# PT.net
KiCad netlist of a schematic drawn in EAGLE
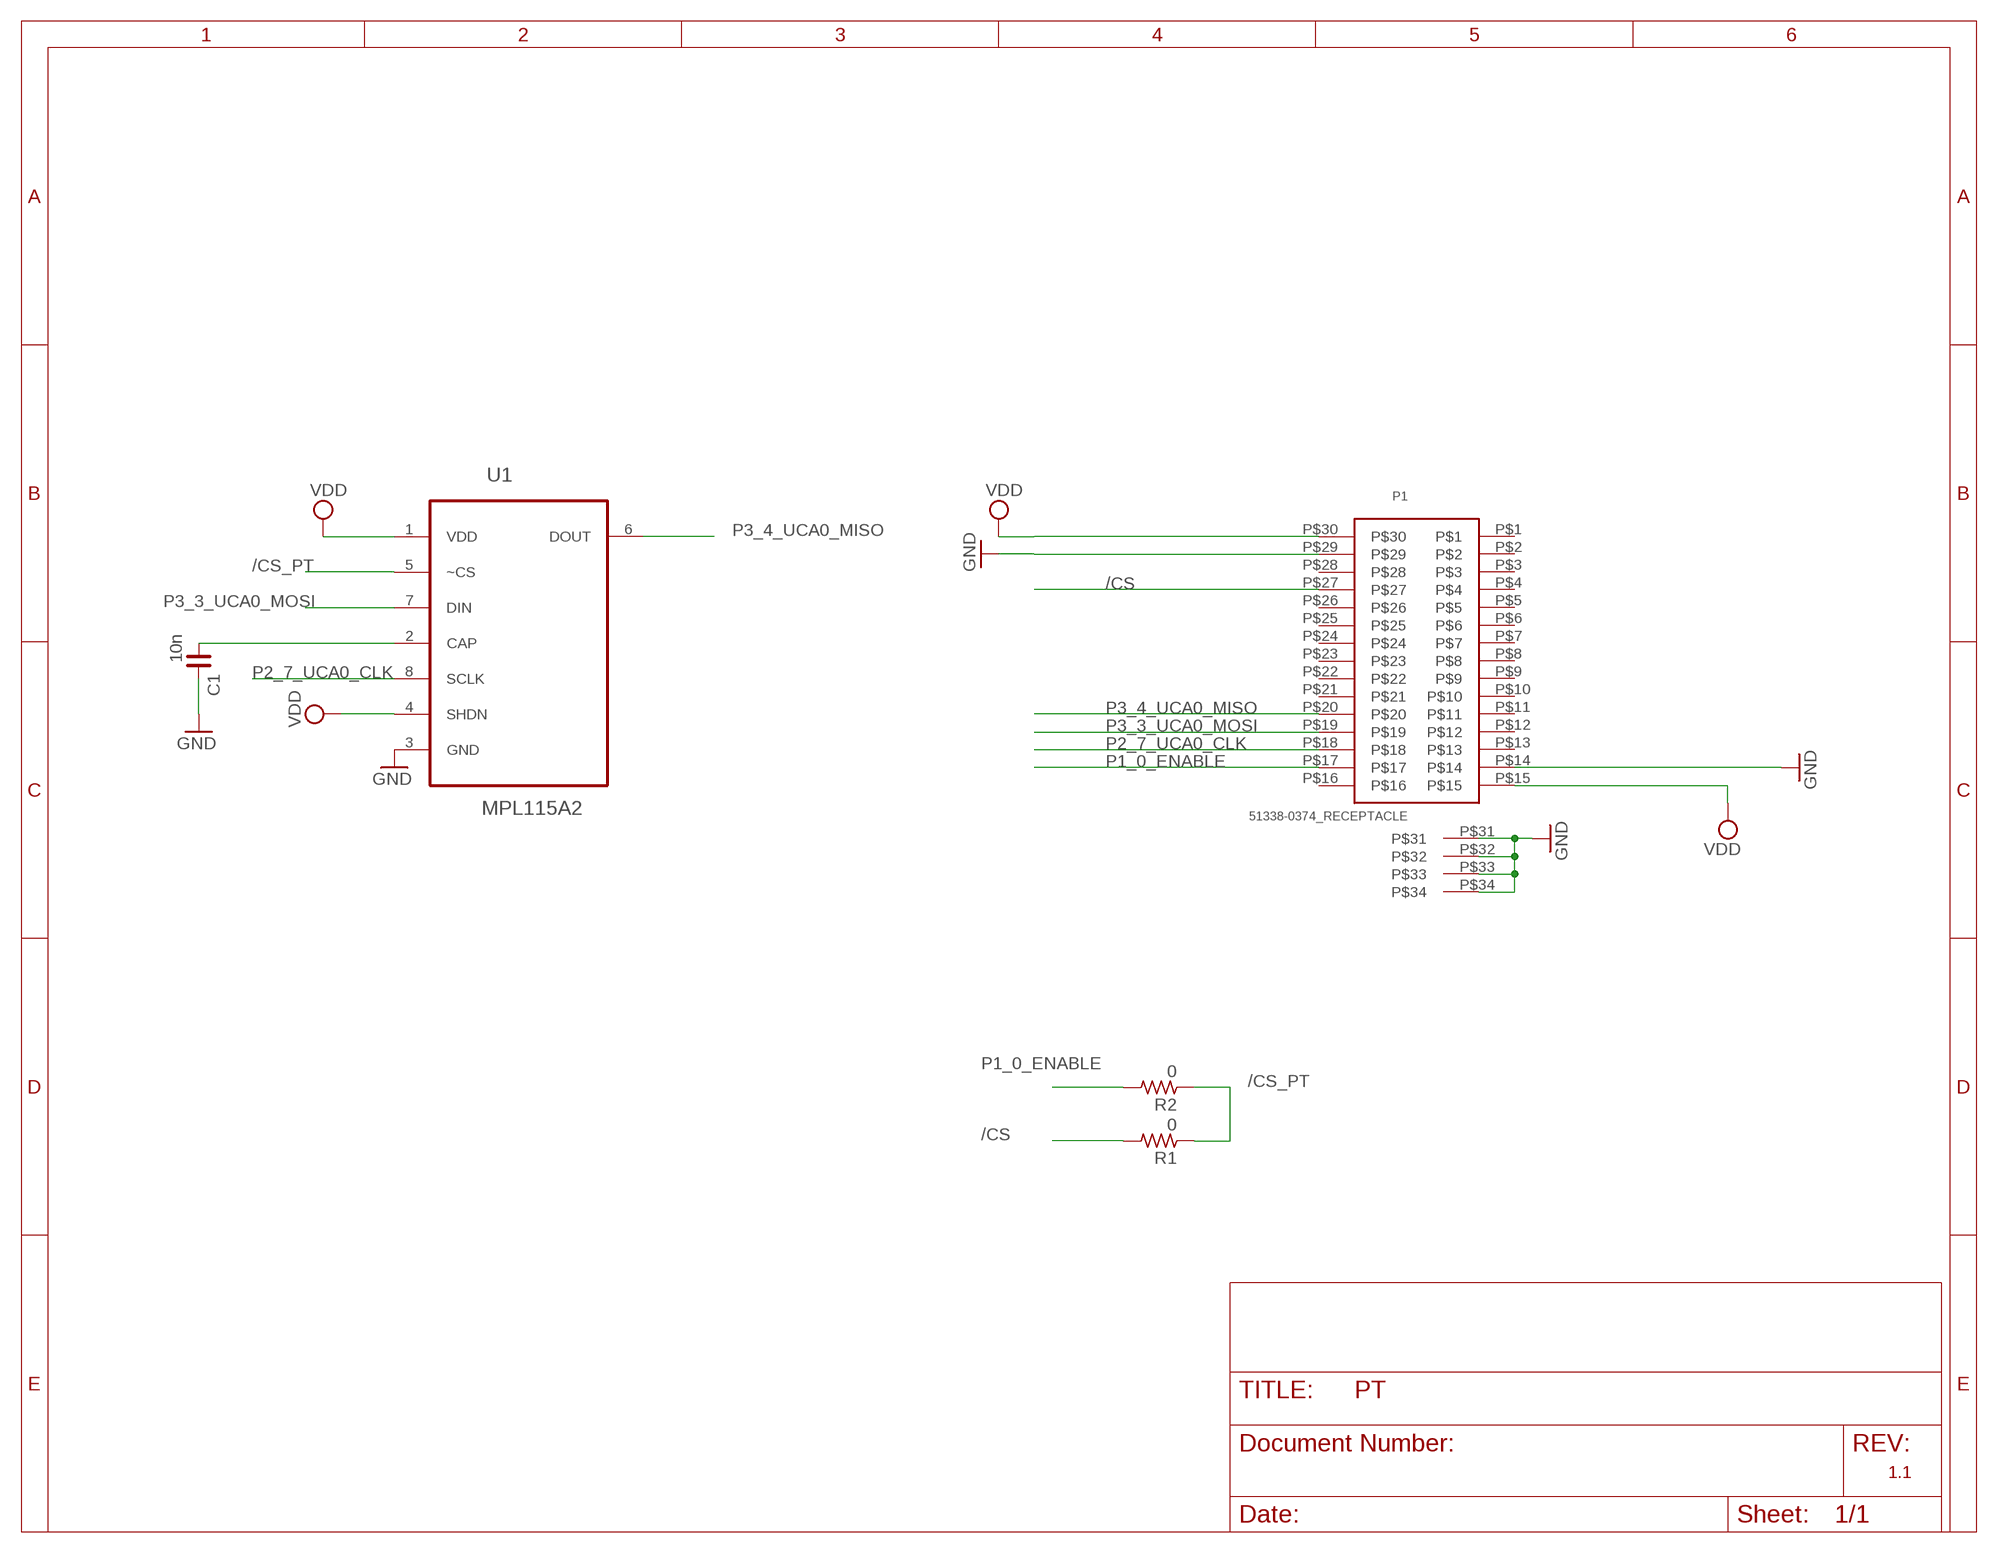
[diagram p0: schematic, sheet 1]

(export (version "E")
  (design (tool "Eeschema 10.0.6"))
  (components
    (comp (ref "C1")
      (value "10n")
      (footprint "eagle-import:C0402")
      (libsource (lib "eagle-import") (part "C_0402"))
    )
    (comp (ref "P1")
      (value "51338-0374_RECEPTACLE")
      (footprint "eagle-import:51338-0374_RECEPTACLE")
      (libsource (lib "eagle-import") (part "51338-0374_RECEPTACLE"))
    )
    (comp (ref "R1")
      (value "0")
      (footprint "eagle-import:R0402")
      (libsource (lib "eagle-import") (part "R_0402"))
    )
    (comp (ref "R2")
      (value "0")
      (footprint "eagle-import:R0402")
      (libsource (lib "eagle-import") (part "R_0402"))
    )
    (comp (ref "U1")
      (value "MPL115A2")
      (footprint "eagle-import:LGA8R125P0X4_500X300X120")
      (libsource (lib "eagle-import") (part "MPL115A2"))
    )
  )
  (nets
    (net (code "1") (name "/P1_0_ENABLE") (class "Default")
      (node (ref "P1") (pin "P$17") (pinfunction "P$17_P$17") (pintype "bidirectional"))
      (node (ref "R2") (pin "2") (pinfunction "2_2") (pintype "passive"))
    )
    (net (code "2") (name "/P2_7_UCA0_CLK") (class "Default")
      (node (ref "P1") (pin "P$18") (pinfunction "P$18_P$18") (pintype "bidirectional"))
      (node (ref "U1") (pin "8") (pinfunction "SCLK_8") (pintype "input"))
    )
    (net (code "3") (name "/P3_3_UCA0_MOSI") (class "Default")
      (node (ref "P1") (pin "P$19") (pinfunction "P$19_P$19") (pintype "bidirectional"))
      (node (ref "U1") (pin "7") (pinfunction "DIN_7") (pintype "input"))
    )
    (net (code "4") (name "/P3_4_UCA0_MISO") (class "Default")
      (node (ref "P1") (pin "P$20") (pinfunction "P$20_P$20") (pintype "bidirectional"))
      (node (ref "U1") (pin "6") (pinfunction "DOUT_6") (pintype "output"))
    )
    (net (code "5") (name "/{slash}CS") (class "Default")
      (node (ref "P1") (pin "P$27") (pinfunction "P$27_P$27") (pintype "bidirectional"))
      (node (ref "R1") (pin "2") (pinfunction "2_2") (pintype "passive"))
    )
    (net (code "6") (name "/{slash}CS_PT") (class "Default")
      (node (ref "R1") (pin "1") (pinfunction "1_1") (pintype "passive"))
      (node (ref "R2") (pin "1") (pinfunction "1_1") (pintype "passive"))
      (node (ref "U1") (pin "5") (pinfunction "~{CS}_5") (pintype "input"))
    )
    (net (code "7") (name "GND") (class "Default")
      (node (ref "C1") (pin "2") (pinfunction "2_2") (pintype "passive"))
      (node (ref "P1") (pin "P$14") (pinfunction "P$14_P$14") (pintype "bidirectional"))
      (node (ref "P1") (pin "P$29") (pinfunction "P$29_P$29") (pintype "bidirectional"))
      (node (ref "P1") (pin "P$31") (pinfunction "P$31_P$31") (pintype "bidirectional"))
      (node (ref "P1") (pin "P$32") (pinfunction "P$32_P$32") (pintype "bidirectional"))
      (node (ref "P1") (pin "P$33") (pinfunction "P$33_P$33") (pintype "bidirectional"))
      (node (ref "P1") (pin "P$34") (pinfunction "P$34_P$34") (pintype "bidirectional"))
      (node (ref "U1") (pin "3") (pinfunction "GND_3") (pintype "passive"))
    )
    (net (code "8") (name "Net-(U1-CAP)") (class "Default")
      (node (ref "C1") (pin "1") (pinfunction "1_1") (pintype "passive"))
      (node (ref "U1") (pin "2") (pinfunction "CAP_2") (pintype "input"))
    )
    (net (code "9") (name "VDD") (class "Default")
      (node (ref "P1") (pin "P$15") (pinfunction "P$15_P$15") (pintype "bidirectional"))
      (node (ref "P1") (pin "P$30") (pinfunction "P$30_P$30") (pintype "bidirectional"))
      (node (ref "U1") (pin "1") (pinfunction "VDD_1") (pintype "power_in"))
      (node (ref "U1") (pin "4") (pinfunction "SHDN_4") (pintype "input"))
    )
    (net (code "10") (name "unconnected-(P1-PadP$1)") (class "Default")
      (node (ref "P1") (pin "P$1") (pinfunction "P$1_P$1") (pintype "bidirectional"))
    )
    (net (code "11") (name "unconnected-(P1-PadP$2)") (class "Default")
      (node (ref "P1") (pin "P$2") (pinfunction "P$2_P$2") (pintype "bidirectional"))
    )
    (net (code "12") (name "unconnected-(P1-PadP$3)") (class "Default")
      (node (ref "P1") (pin "P$3") (pinfunction "P$3_P$3") (pintype "bidirectional"))
    )
    (net (code "13") (name "unconnected-(P1-PadP$4)") (class "Default")
      (node (ref "P1") (pin "P$4") (pinfunction "P$4_P$4") (pintype "bidirectional"))
    )
    (net (code "14") (name "unconnected-(P1-PadP$5)") (class "Default")
      (node (ref "P1") (pin "P$5") (pinfunction "P$5_P$5") (pintype "bidirectional"))
    )
    (net (code "15") (name "unconnected-(P1-PadP$6)") (class "Default")
      (node (ref "P1") (pin "P$6") (pinfunction "P$6_P$6") (pintype "bidirectional"))
    )
    (net (code "16") (name "unconnected-(P1-PadP$7)") (class "Default")
      (node (ref "P1") (pin "P$7") (pinfunction "P$7_P$7") (pintype "bidirectional"))
    )
    (net (code "17") (name "unconnected-(P1-PadP$8)") (class "Default")
      (node (ref "P1") (pin "P$8") (pinfunction "P$8_P$8") (pintype "bidirectional"))
    )
    (net (code "18") (name "unconnected-(P1-PadP$9)") (class "Default")
      (node (ref "P1") (pin "P$9") (pinfunction "P$9_P$9") (pintype "bidirectional"))
    )
    (net (code "19") (name "unconnected-(P1-PadP$10)") (class "Default")
      (node (ref "P1") (pin "P$10") (pinfunction "P$10_P$10") (pintype "bidirectional"))
    )
    (net (code "20") (name "unconnected-(P1-PadP$11)") (class "Default")
      (node (ref "P1") (pin "P$11") (pinfunction "P$11_P$11") (pintype "bidirectional"))
    )
    (net (code "21") (name "unconnected-(P1-PadP$12)") (class "Default")
      (node (ref "P1") (pin "P$12") (pinfunction "P$12_P$12") (pintype "bidirectional"))
    )
    (net (code "22") (name "unconnected-(P1-PadP$13)") (class "Default")
      (node (ref "P1") (pin "P$13") (pinfunction "P$13_P$13") (pintype "bidirectional"))
    )
    (net (code "23") (name "unconnected-(P1-PadP$16)") (class "Default")
      (node (ref "P1") (pin "P$16") (pinfunction "P$16_P$16") (pintype "bidirectional"))
    )
    (net (code "24") (name "unconnected-(P1-PadP$21)") (class "Default")
      (node (ref "P1") (pin "P$21") (pinfunction "P$21_P$21") (pintype "bidirectional"))
    )
    (net (code "25") (name "unconnected-(P1-PadP$22)") (class "Default")
      (node (ref "P1") (pin "P$22") (pinfunction "P$22_P$22") (pintype "bidirectional"))
    )
    (net (code "26") (name "unconnected-(P1-PadP$23)") (class "Default")
      (node (ref "P1") (pin "P$23") (pinfunction "P$23_P$23") (pintype "bidirectional"))
    )
    (net (code "27") (name "unconnected-(P1-PadP$24)") (class "Default")
      (node (ref "P1") (pin "P$24") (pinfunction "P$24_P$24") (pintype "bidirectional"))
    )
    (net (code "28") (name "unconnected-(P1-PadP$25)") (class "Default")
      (node (ref "P1") (pin "P$25") (pinfunction "P$25_P$25") (pintype "bidirectional"))
    )
    (net (code "29") (name "unconnected-(P1-PadP$26)") (class "Default")
      (node (ref "P1") (pin "P$26") (pinfunction "P$26_P$26") (pintype "bidirectional"))
    )
    (net (code "30") (name "unconnected-(P1-PadP$28)") (class "Default")
      (node (ref "P1") (pin "P$28") (pinfunction "P$28_P$28") (pintype "bidirectional"))
    )
  )
)
